# IMX7S_CPU_INTERFACES_2.net
KiCad netlist of a schematic drawn in Altium Designer
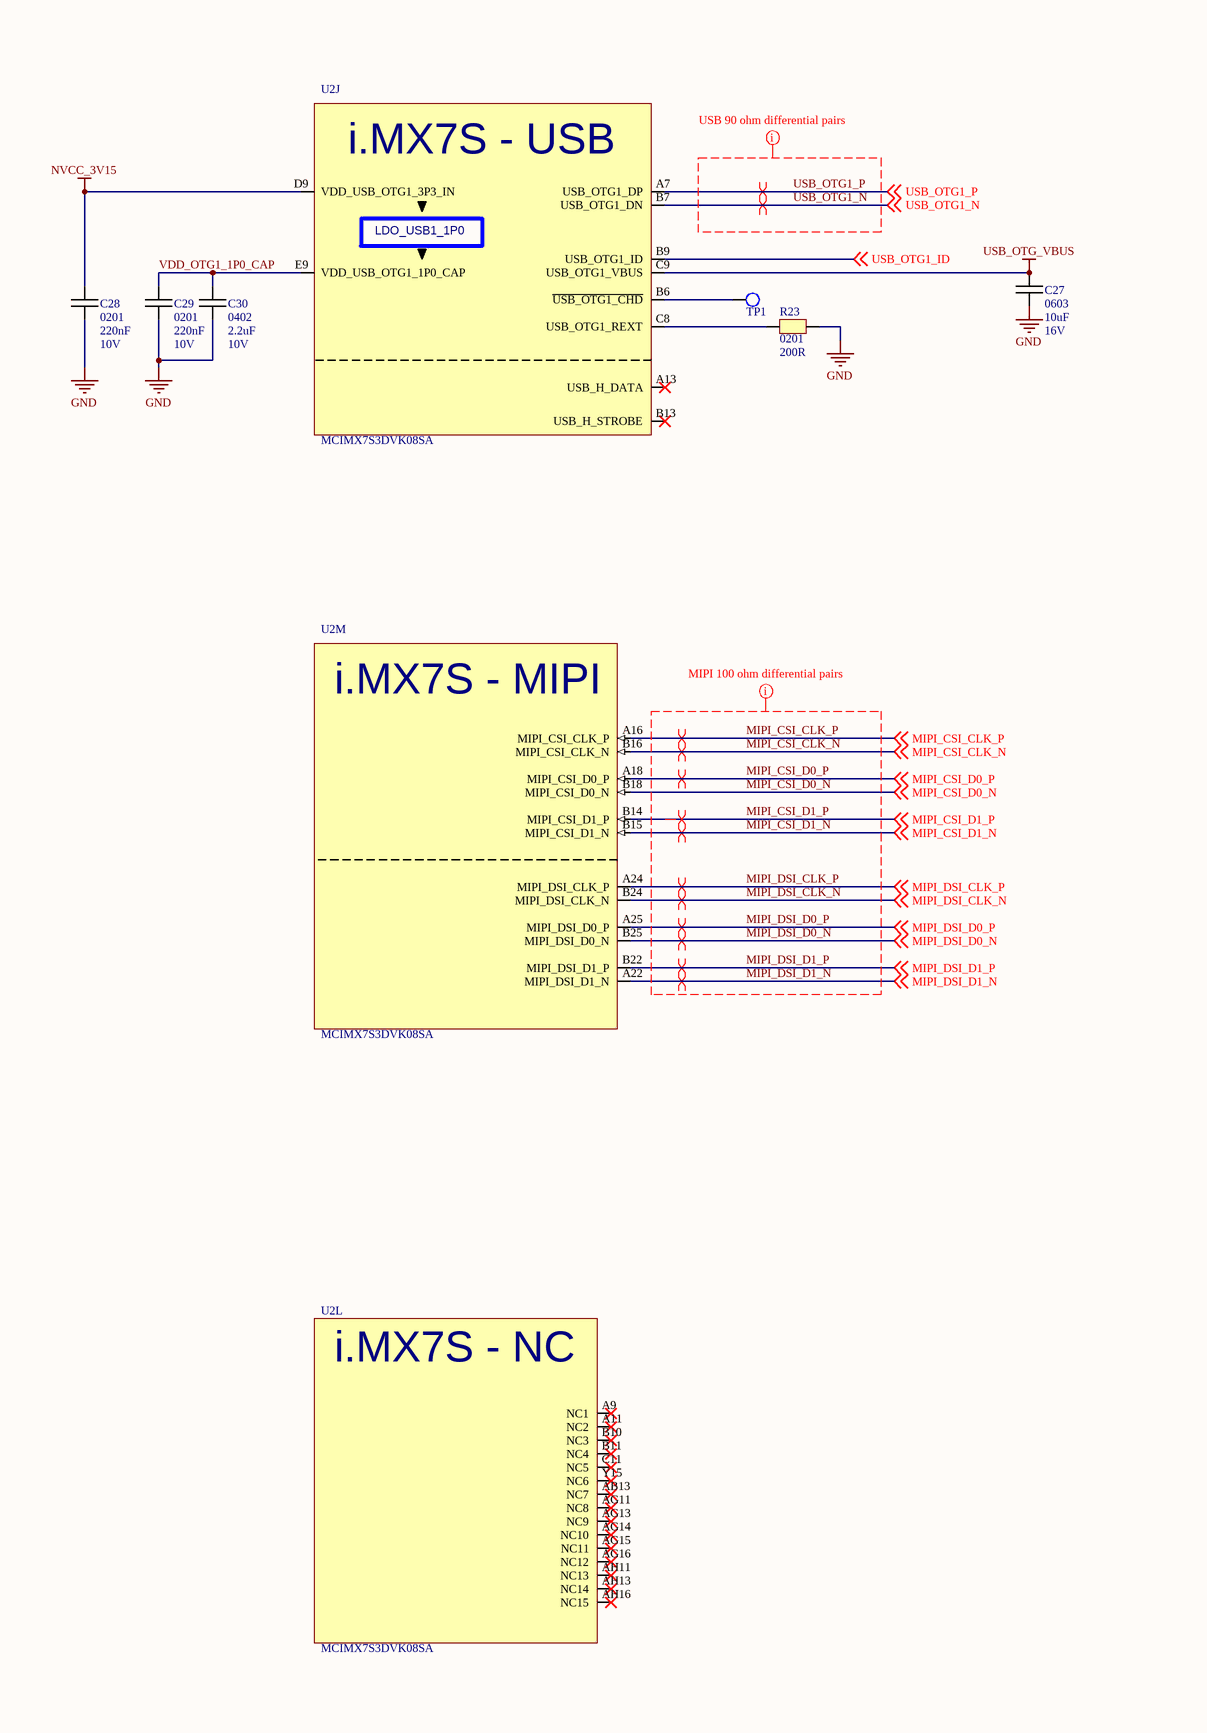
[diagram p0: IMX7S_CPU_INTERFACES_2.SchDoc, left]
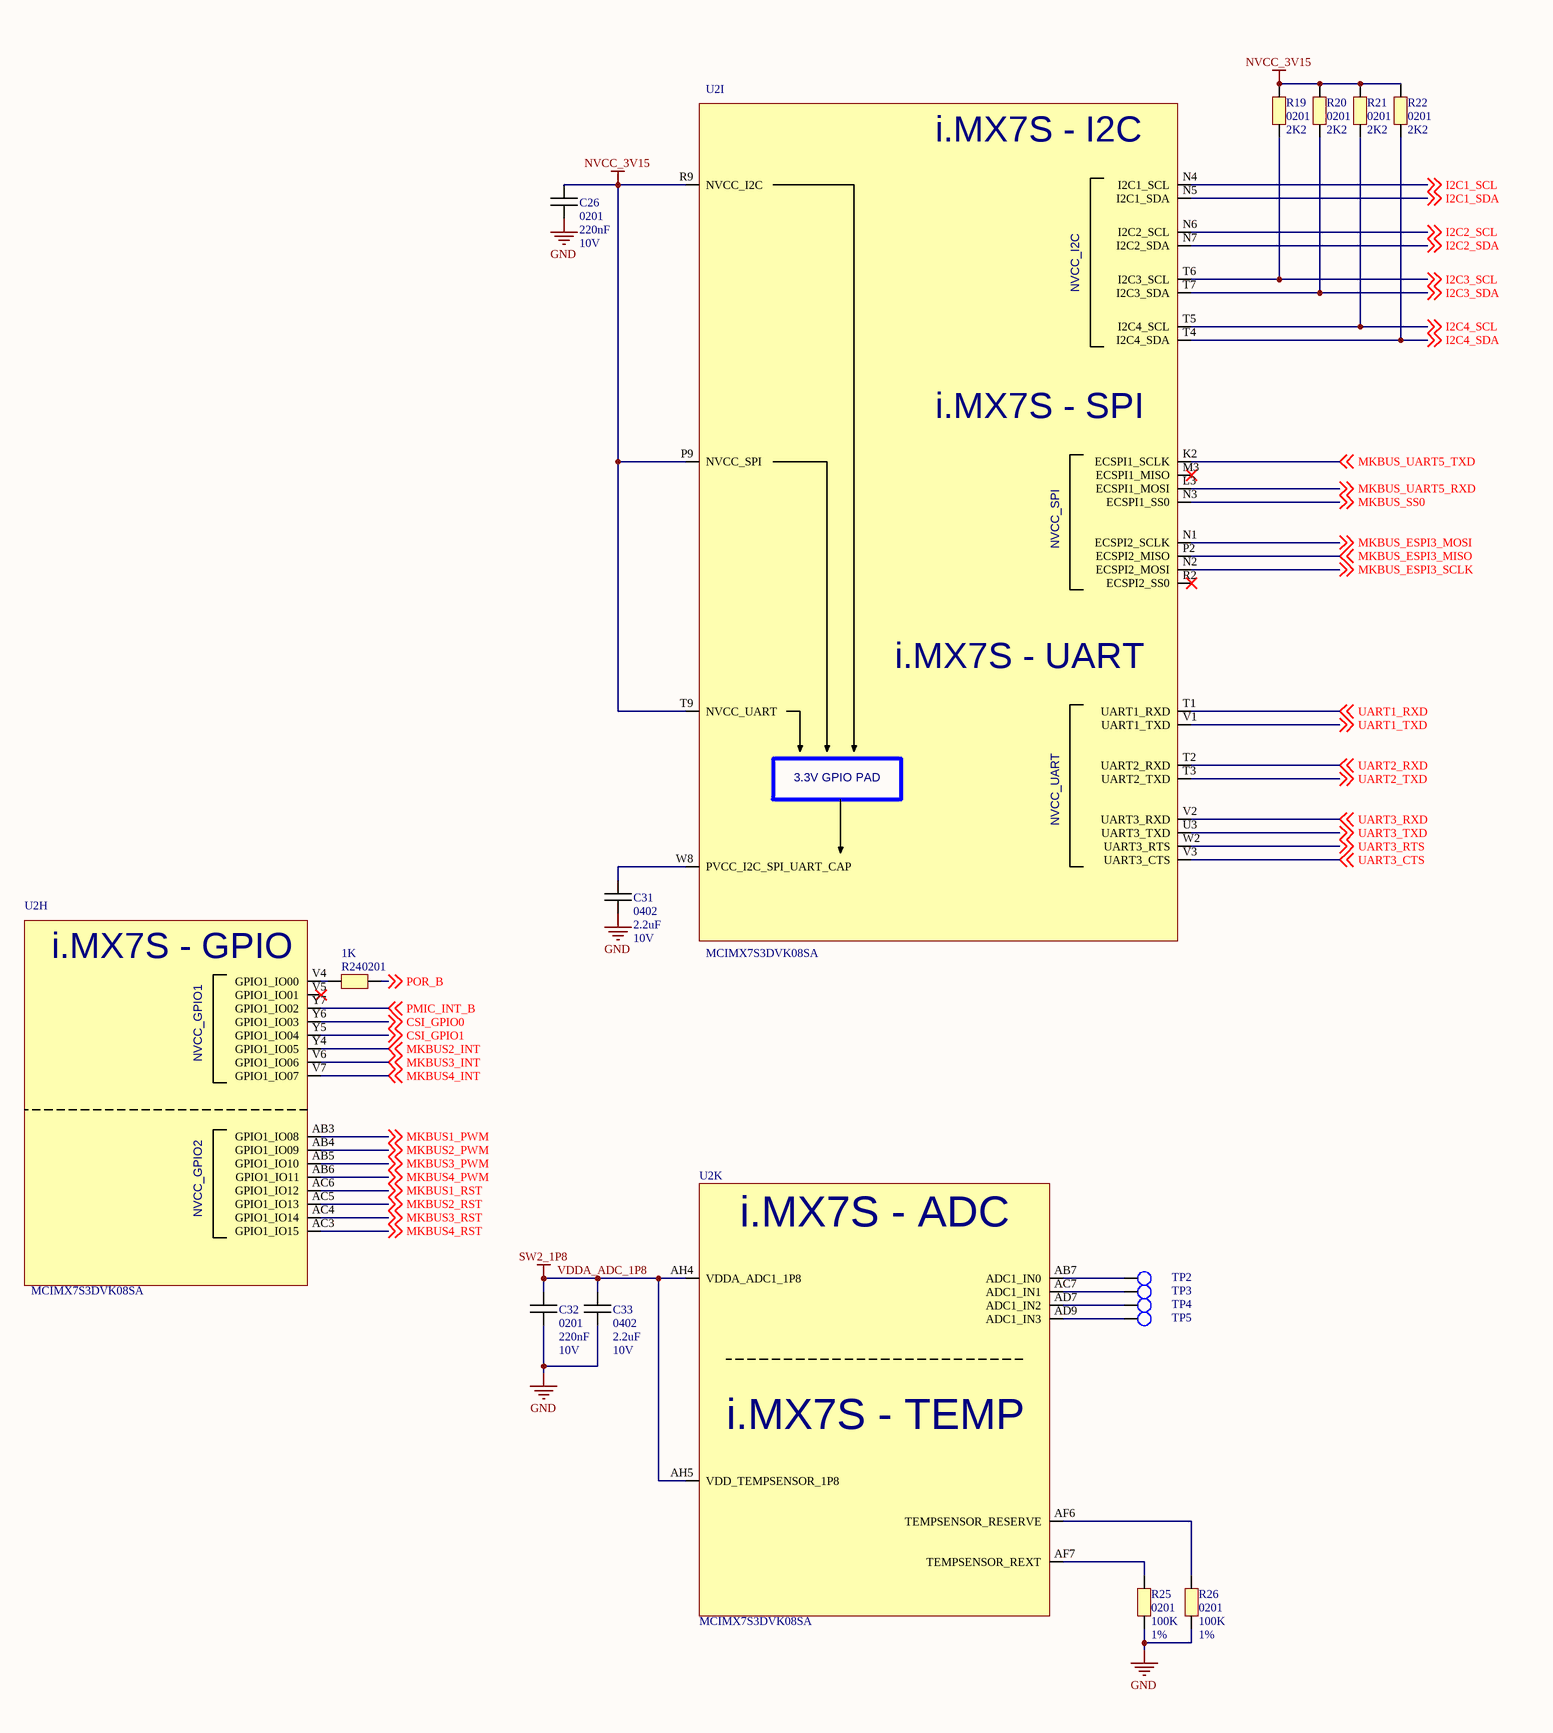
[diagram p1: IMX7S_CPU_INTERFACES_2.SchDoc, right]

(export (version "E")
  (design (tool "Eeschema 10.0.6"))
  (components
    (comp (ref "C26")
      (value "220nF")
      (footprint "C0201")
      (fields
        (field (name "PACKAGE") "0201")
        (field (name "VOLTAGE") "10V")
        (field (name "TOLERANCE") "10%")
        (field (name "Comment") "C0201")
      )
      (libsource (lib "Schlib_IMX7") (part "C0201"))
    )
    (comp (ref "C27")
      (value "10uF")
      (footprint "C0603")
      (description "Cap Ceramic 10uF 10V X5R 10% SMD 0603 85C Paper T/R")
      (fields
        (field (name "PACKAGE") "0603")
        (field (name "VOLTAGE") "16V")
        (field (name "TOLERANCE") "10%")
        (field (name "Comment") "C0603")
      )
      (libsource (lib "Schlib_IMX7") (part "C0603"))
    )
    (comp (ref "C28")
      (value "220nF")
      (footprint "C0201")
      (fields
        (field (name "PACKAGE") "0201")
        (field (name "VOLTAGE") "10V")
        (field (name "TOLERANCE") "10%")
        (field (name "Comment") "C0201")
      )
      (libsource (lib "Schlib_IMX7") (part "C0201"))
    )
    (comp (ref "C29")
      (value "220nF")
      (footprint "C0201")
      (fields
        (field (name "PACKAGE") "0201")
        (field (name "VOLTAGE") "10V")
        (field (name "TOLERANCE") "10%")
        (field (name "Comment") "C0201")
      )
      (libsource (lib "Schlib_IMX7") (part "C0201"))
    )
    (comp (ref "C30")
      (value "2.2uF")
      (footprint "C0402")
      (description "Cap Ceramic 2.2uF 10V X5R 10% SMD 0402 85C Paper T/R")
      (fields
        (field (name "PACKAGE") "0402")
        (field (name "VOLTAGE") "10V")
        (field (name "TOLERANCE") "10%")
        (field (name "Comment") "C0402")
      )
      (libsource (lib "Schlib_IMX7") (part "C0402"))
    )
    (comp (ref "C31")
      (value "2.2uF")
      (footprint "C0402")
      (fields
        (field (name "PACKAGE") "0402")
        (field (name "VOLTAGE") "10V")
        (field (name "TOLERANCE") "20%")
        (field (name "Comment") "C0402")
      )
      (libsource (lib "Schlib_IMX7") (part "C0402"))
    )
    (comp (ref "C32")
      (value "220nF")
      (footprint "C0201")
      (fields
        (field (name "PACKAGE") "0201")
        (field (name "VOLTAGE") "10V")
        (field (name "TOLERANCE") "10%")
        (field (name "Comment") "C0201")
      )
      (libsource (lib "Schlib_IMX7") (part "C0201"))
    )
    (comp (ref "C33")
      (value "2.2uF")
      (footprint "C0402")
      (fields
        (field (name "PACKAGE") "0402")
        (field (name "VOLTAGE") "10V")
        (field (name "TOLERANCE") "20%")
        (field (name "Comment") "C0402")
      )
      (libsource (lib "Schlib_IMX7") (part "C0402"))
    )
    (comp (ref "R19")
      (value "2K2")
      (footprint "R0201")
      (description "MULTICOMP - MCRE000148 - RES, 2K2, 1%, 0.05W, 0201, THICK FILM")
      (fields (field (name "PACKAGE") "0201") (field (name "VOLTAGE") "0V") (field (name "TOLERANCE") "1%"))
      (libsource (lib "Schlib_IMX7") (part "R0201"))
    )
    (comp (ref "R20")
      (value "2K2")
      (footprint "R0201")
      (description "MULTICOMP - MCRE000148 - RES, 2K2, 1%, 0.05W, 0201, THICK FILM")
      (fields (field (name "PACKAGE") "0201") (field (name "VOLTAGE") "0V") (field (name "TOLERANCE") "1%"))
      (libsource (lib "Schlib_IMX7") (part "R0201"))
    )
    (comp (ref "R21")
      (value "2K2")
      (footprint "R0201")
      (description "MULTICOMP - MCRE000148 - RES, 2K2, 1%, 0.05W, 0201, THICK FILM")
      (fields (field (name "PACKAGE") "0201") (field (name "VOLTAGE") "0V") (field (name "TOLERANCE") "1%"))
      (libsource (lib "Schlib_IMX7") (part "R0201"))
    )
    (comp (ref "R22")
      (value "2K2")
      (footprint "R0201")
      (description "MULTICOMP - MCRE000148 - RES, 2K2, 1%, 0.05W, 0201, THICK FILM")
      (fields (field (name "PACKAGE") "0201") (field (name "VOLTAGE") "0V") (field (name "TOLERANCE") "1%"))
      (libsource (lib "Schlib_IMX7") (part "R0201"))
    )
    (comp (ref "R23")
      (value "200R")
      (footprint "R0201")
      (fields
        (field (name "PACKAGE") "0201")
        (field (name "VOLTAGE") "0V")
        (field (name "TOLERANCE") "1%")
        (field (name "Comment") "R0201")
      )
      (libsource (lib "") (part "R0201_1"))
    )
    (comp (ref "R24")
      (value "1K")
      (footprint "R0201")
      (fields (field (name "PACKAGE") "0201") (field (name "VOLTAGE") "1%") (field (name "Comment") "R0201"))
      (libsource (lib "") (part "R0201_2"))
    )
    (comp (ref "R25")
      (value "100K")
      (footprint "R0201")
      (description "MULTICOMP - MCWR02X1003FAL - RES, 100K, 1%, 0.05W, THICK FILM")
      (fields
        (field (name "PACKAGE") "0201")
        (field (name "VOLTAGE") "1%")
        (field (name "TOLERANCE") "1%")
        (field (name "Comment") "R0201")
      )
      (libsource (lib "Schlib_IMX7") (part "R0201"))
    )
    (comp (ref "R26")
      (value "100K")
      (footprint "R0201")
      (description "MULTICOMP - MCWR02X1003FAL - RES, 100K, 1%, 0.05W, THICK FILM")
      (fields
        (field (name "PACKAGE") "0201")
        (field (name "VOLTAGE") "1%")
        (field (name "TOLERANCE") "1%")
        (field (name "Comment") "R0201")
      )
      (libsource (lib "Schlib_IMX7") (part "R0201"))
    )
    (comp (ref "TP1")
      (value "TestPoint")
      (footprint "TESTPOINT")
      (libsource (lib "Schlib_IMX7") (part "TestPoint"))
    )
    (comp (ref "TP2")
      (value "TestPoint")
      (footprint "TESTPOINT")
      (libsource (lib "Schlib_IMX7") (part "TestPoint"))
    )
    (comp (ref "TP3")
      (value "TestPoint")
      (footprint "TESTPOINT")
      (libsource (lib "Schlib_IMX7") (part "TestPoint"))
    )
    (comp (ref "TP4")
      (value "TestPoint")
      (footprint "TESTPOINT")
      (libsource (lib "Schlib_IMX7") (part "TestPoint"))
    )
    (comp (ref "TP5")
      (value "TestPoint")
      (footprint "TESTPOINT")
      (libsource (lib "Schlib_IMX7") (part "TestPoint"))
    )
    (comp (ref "U2")
      (value "MCIMX7S3DVK08SA")
      (footprint "BGA 488 PIN")
      (libsource (lib "Schlib_IMX7") (part "MCIMX7S3DVK08SD"))
    )
  )
  (nets
    (net (code "1") (name "/VDD_OTG1_1P0_CAP") (class "Default")
      (node (ref "C29") (pin "2") (pinfunction "2_2") (pintype "passive"))
      (node (ref "C30") (pin "2") (pinfunction "2_2") (pintype "passive"))
      (node (ref "U2") (pin "E9") (pinfunction "VDD_USB_OTG1_1P0_CAP_E9") (pintype "passive"))
    )
    (net (code "2") (name "CSI_GPIO0") (class "Default")
      (node (ref "U2") (pin "Y6") (pinfunction "GPIO1_IO03_Y6") (pintype "passive"))
    )
    (net (code "3") (name "CSI_GPIO1") (class "Default")
      (node (ref "U2") (pin "Y5") (pinfunction "GPIO1_IO04_Y5") (pintype "passive"))
    )
    (net (code "4") (name "GND") (class "Default")
      (node (ref "C26") (pin "1") (pinfunction "1_1") (pintype "passive"))
      (node (ref "C27") (pin "1") (pinfunction "1_1") (pintype "passive"))
      (node (ref "C28") (pin "1") (pinfunction "1_1") (pintype "passive"))
      (node (ref "C29") (pin "1") (pinfunction "1_1") (pintype "passive"))
      (node (ref "C30") (pin "1") (pinfunction "1_1") (pintype "passive"))
      (node (ref "C31") (pin "1") (pinfunction "1_1") (pintype "passive"))
      (node (ref "C32") (pin "1") (pinfunction "1_1") (pintype "passive"))
      (node (ref "C33") (pin "1") (pinfunction "1_1") (pintype "passive"))
      (node (ref "R23") (pin "2") (pinfunction "2_2") (pintype "passive"))
      (node (ref "R25") (pin "1") (pinfunction "1_1") (pintype "passive"))
      (node (ref "R26") (pin "1") (pinfunction "1_1") (pintype "passive"))
    )
    (net (code "5") (name "I2C1_SCL") (class "Default")
      (node (ref "U2") (pin "N4") (pinfunction "I2C1_SCL_N4") (pintype "passive"))
    )
    (net (code "6") (name "I2C1_SDA") (class "Default")
      (node (ref "U2") (pin "N5") (pinfunction "I2C1_SDA_N5") (pintype "passive"))
    )
    (net (code "7") (name "I2C2_SCL") (class "Default")
      (node (ref "U2") (pin "N6") (pinfunction "I2C2_SCL_N6") (pintype "passive"))
    )
    (net (code "8") (name "I2C2_SDA") (class "Default")
      (node (ref "U2") (pin "N7") (pinfunction "I2C2_SDA_N7") (pintype "passive"))
    )
    (net (code "9") (name "I2C3_SCL") (class "Default")
      (node (ref "R19") (pin "1") (pinfunction "1_1") (pintype "passive"))
      (node (ref "U2") (pin "T6") (pinfunction "I2C3_SCL_T6") (pintype "passive"))
    )
    (net (code "10") (name "I2C3_SDA") (class "Default")
      (node (ref "R20") (pin "1") (pinfunction "1_1") (pintype "passive"))
      (node (ref "U2") (pin "T7") (pinfunction "I2C3_SDA_T7") (pintype "passive"))
    )
    (net (code "11") (name "I2C4_SCL") (class "Default")
      (node (ref "R21") (pin "1") (pinfunction "1_1") (pintype "passive"))
      (node (ref "U2") (pin "T5") (pinfunction "I2C4_SCL_T5") (pintype "passive"))
    )
    (net (code "12") (name "I2C4_SDA") (class "Default")
      (node (ref "R22") (pin "1") (pinfunction "1_1") (pintype "passive"))
      (node (ref "U2") (pin "T4") (pinfunction "I2C4_SDA_T4") (pintype "passive"))
    )
    (net (code "13") (name "MIPI_CSI_CLK_N") (class "Default")
      (node (ref "U2") (pin "B16") (pinfunction "MIPI_CSI_CLK_N_B16") (pintype "input"))
    )
    (net (code "14") (name "MIPI_CSI_CLK_P") (class "Default")
      (node (ref "U2") (pin "A16") (pinfunction "MIPI_CSI_CLK_P_A16") (pintype "input"))
    )
    (net (code "15") (name "MIPI_CSI_D0_N") (class "Default")
      (node (ref "U2") (pin "B18") (pinfunction "MIPI_CSI_D0_N_B18") (pintype "input"))
    )
    (net (code "16") (name "MIPI_CSI_D0_P") (class "Default")
      (node (ref "U2") (pin "A18") (pinfunction "MIPI_CSI_D0_P_A18") (pintype "input"))
    )
    (net (code "17") (name "MIPI_CSI_D1_N") (class "Default")
      (node (ref "U2") (pin "B15") (pinfunction "MIPI_CSI_D1_N_B15") (pintype "input"))
    )
    (net (code "18") (name "MIPI_CSI_D1_P") (class "Default")
      (node (ref "U2") (pin "B14") (pinfunction "MIPI_CSI_D1_P_B14") (pintype "input"))
    )
    (net (code "19") (name "MIPI_DSI_CLK_N") (class "Default")
      (node (ref "U2") (pin "B24") (pinfunction "MIPI_DSI_CLK_N_B24") (pintype "passive"))
    )
    (net (code "20") (name "MIPI_DSI_CLK_P") (class "Default")
      (node (ref "U2") (pin "A24") (pinfunction "MIPI_DSI_CLK_P_A24") (pintype "passive"))
    )
    (net (code "21") (name "MIPI_DSI_D0_N") (class "Default")
      (node (ref "U2") (pin "B25") (pinfunction "MIPI_DSI_D0_N_B25") (pintype "passive"))
    )
    (net (code "22") (name "MIPI_DSI_D0_P") (class "Default")
      (node (ref "U2") (pin "A25") (pinfunction "MIPI_DSI_D0_P_A25") (pintype "passive"))
    )
    (net (code "23") (name "MIPI_DSI_D1_N") (class "Default")
      (node (ref "U2") (pin "A22") (pinfunction "MIPI_DSI_D1_N_A22") (pintype "passive"))
    )
    (net (code "24") (name "MIPI_DSI_D1_P") (class "Default")
      (node (ref "U2") (pin "B22") (pinfunction "MIPI_DSI_D1_P_B22") (pintype "passive"))
    )
    (net (code "25") (name "MKBUS1_PWM") (class "Default")
      (node (ref "U2") (pin "AB3") (pinfunction "GPIO1_IO08_AB3") (pintype "passive"))
    )
    (net (code "26") (name "MKBUS1_RST") (class "Default")
      (node (ref "U2") (pin "AC6") (pinfunction "GPIO1_IO12_AC6") (pintype "passive"))
    )
    (net (code "27") (name "MKBUS2_INT") (class "Default")
      (node (ref "U2") (pin "Y4") (pinfunction "GPIO1_IO05_Y4") (pintype "passive"))
    )
    (net (code "28") (name "MKBUS2_PWM") (class "Default")
      (node (ref "U2") (pin "AB4") (pinfunction "GPIO1_IO09_AB4") (pintype "passive"))
    )
    (net (code "29") (name "MKBUS2_RST") (class "Default")
      (node (ref "U2") (pin "AC5") (pinfunction "GPIO1_IO13_AC5") (pintype "passive"))
    )
    (net (code "30") (name "MKBUS3_INT") (class "Default")
      (node (ref "U2") (pin "V6") (pinfunction "GPIO1_IO06_V6") (pintype "passive"))
    )
    (net (code "31") (name "MKBUS3_PWM") (class "Default")
      (node (ref "U2") (pin "AB5") (pinfunction "GPIO1_IO10_AB5") (pintype "passive"))
    )
    (net (code "32") (name "MKBUS3_RST") (class "Default")
      (node (ref "U2") (pin "AC4") (pinfunction "GPIO1_IO14_AC4") (pintype "passive"))
    )
    (net (code "33") (name "MKBUS4_INT") (class "Default")
      (node (ref "U2") (pin "V7") (pinfunction "GPIO1_IO07_V7") (pintype "passive"))
    )
    (net (code "34") (name "MKBUS4_PWM") (class "Default")
      (node (ref "U2") (pin "AB6") (pinfunction "GPIO1_IO11_AB6") (pintype "passive"))
    )
    (net (code "35") (name "MKBUS4_RST") (class "Default")
      (node (ref "U2") (pin "AC3") (pinfunction "GPIO1_IO15_AC3") (pintype "passive"))
    )
    (net (code "36") (name "MKBUS_ESPI3_MISO") (class "Default")
      (node (ref "U2") (pin "P2") (pinfunction "ECSPI2_MISO_P2") (pintype "passive"))
    )
    (net (code "37") (name "MKBUS_ESPI3_MOSI") (class "Default")
      (node (ref "U2") (pin "N1") (pinfunction "ECSPI2_SCLK_N1") (pintype "passive"))
    )
    (net (code "38") (name "MKBUS_ESPI3_SCLK") (class "Default")
      (node (ref "U2") (pin "N2") (pinfunction "ECSPI2_MOSI_N2") (pintype "passive"))
    )
    (net (code "39") (name "MKBUS_SS0") (class "Default")
      (node (ref "U2") (pin "N3") (pinfunction "ECSPI1_SS0_N3") (pintype "passive"))
    )
    (net (code "40") (name "MKBUS_UART5_RXD") (class "Default")
      (node (ref "U2") (pin "L3") (pinfunction "ECSPI1_MOSI_L3") (pintype "passive"))
    )
    (net (code "41") (name "MKBUS_UART5_TXD") (class "Default")
      (node (ref "U2") (pin "K2") (pinfunction "ECSPI1_SCLK_K2") (pintype "passive"))
    )
    (net (code "42") (name "NVCC_3V15") (class "Default")
      (node (ref "C26") (pin "2") (pinfunction "2_2") (pintype "passive"))
      (node (ref "C28") (pin "2") (pinfunction "2_2") (pintype "passive"))
      (node (ref "R19") (pin "2") (pinfunction "2_2") (pintype "passive"))
      (node (ref "R20") (pin "2") (pinfunction "2_2") (pintype "passive"))
      (node (ref "R21") (pin "2") (pinfunction "2_2") (pintype "passive"))
      (node (ref "R22") (pin "2") (pinfunction "2_2") (pintype "passive"))
      (node (ref "U2") (pin "D9") (pinfunction "VDD_USB_OTG1_3P3_IN_D9") (pintype "passive"))
      (node (ref "U2") (pin "P9") (pinfunction "NVCC_SPI_P9") (pintype "passive"))
      (node (ref "U2") (pin "R9") (pinfunction "NVCC_I2C_R9") (pintype "passive"))
      (node (ref "U2") (pin "T9") (pinfunction "NVCC_UART_T9") (pintype "passive"))
    )
    (net (code "43") (name "Net-(U2H-GPIO1_IO00)") (class "Default")
      (node (ref "R24") (pin "2") (pinfunction "2_2") (pintype "passive"))
      (node (ref "U2") (pin "V4") (pinfunction "GPIO1_IO00_V4") (pintype "passive"))
    )
    (net (code "44") (name "Net-(U2I-PVCC_I2C_SPI_UART_CAP)") (class "Default")
      (node (ref "C31") (pin "2") (pinfunction "2_2") (pintype "passive"))
      (node (ref "U2") (pin "W8") (pinfunction "PVCC_I2C_SPI_UART_CAP_W8") (pintype "passive"))
    )
    (net (code "45") (name "Net-(U2J-USB_OTG1_REXT)") (class "Default")
      (node (ref "R23") (pin "1") (pinfunction "1_1") (pintype "passive"))
      (node (ref "U2") (pin "C8") (pinfunction "USB_OTG1_REXT_C8") (pintype "passive"))
    )
    (net (code "46") (name "Net-(U2J-~{USB_OTG1_CHD})") (class "Default")
      (node (ref "TP1") (pin "1") (pinfunction "1_1") (pintype "passive"))
      (node (ref "U2") (pin "B6") (pinfunction "~{USB_OTG1_CHD}_B6") (pintype "passive"))
    )
    (net (code "47") (name "Net-(U2K-ADC1_IN0)") (class "Default")
      (node (ref "TP2") (pin "1") (pinfunction "1_1") (pintype "passive"))
      (node (ref "U2") (pin "AB7") (pinfunction "ADC1_IN0_AB7") (pintype "passive"))
    )
    (net (code "48") (name "Net-(U2K-ADC1_IN1)") (class "Default")
      (node (ref "TP3") (pin "1") (pinfunction "1_1") (pintype "passive"))
      (node (ref "U2") (pin "AC7") (pinfunction "ADC1_IN1_AC7") (pintype "passive"))
    )
    (net (code "49") (name "Net-(U2K-ADC1_IN2)") (class "Default")
      (node (ref "TP4") (pin "1") (pinfunction "1_1") (pintype "passive"))
      (node (ref "U2") (pin "AD7") (pinfunction "ADC1_IN2_AD7") (pintype "passive"))
    )
    (net (code "50") (name "Net-(U2K-ADC1_IN3)") (class "Default")
      (node (ref "TP5") (pin "1") (pinfunction "1_1") (pintype "passive"))
      (node (ref "U2") (pin "AD9") (pinfunction "ADC1_IN3_AD9") (pintype "passive"))
    )
    (net (code "51") (name "Net-(U2K-TEMPSENSOR_RESERVE)") (class "Default")
      (node (ref "R26") (pin "2") (pinfunction "2_2") (pintype "passive"))
      (node (ref "U2") (pin "AF6") (pinfunction "TEMPSENSOR_RESERVE_AF6") (pintype "passive"))
    )
    (net (code "52") (name "Net-(U2K-TEMPSENSOR_REXT)") (class "Default")
      (node (ref "R25") (pin "2") (pinfunction "2_2") (pintype "passive"))
      (node (ref "U2") (pin "AF7") (pinfunction "TEMPSENSOR_REXT_AF7") (pintype "passive"))
    )
    (net (code "53") (name "PMIC_INT_B") (class "Default")
      (node (ref "U2") (pin "Y7") (pinfunction "GPIO1_IO02_Y7") (pintype "passive"))
    )
    (net (code "54") (name "POR_B") (class "Default")
      (node (ref "R24") (pin "1") (pinfunction "1_1") (pintype "passive"))
    )
    (net (code "55") (name "SW2_1P8") (class "Default")
      (node (ref "C32") (pin "2") (pinfunction "2_2") (pintype "passive"))
      (node (ref "C33") (pin "2") (pinfunction "2_2") (pintype "passive"))
      (node (ref "U2") (pin "AH4") (pinfunction "VDDA_ADC1_1P8_AH4") (pintype "passive"))
      (node (ref "U2") (pin "AH5") (pinfunction "VDD_TEMPSENSOR_1P8_AH5") (pintype "passive"))
    )
    (net (code "56") (name "UART1_RXD") (class "Default")
      (node (ref "U2") (pin "T1") (pinfunction "UART1_RXD_T1") (pintype "passive"))
    )
    (net (code "57") (name "UART1_TXD") (class "Default")
      (node (ref "U2") (pin "V1") (pinfunction "UART1_TXD_V1") (pintype "passive"))
    )
    (net (code "58") (name "UART2_RXD") (class "Default")
      (node (ref "U2") (pin "T2") (pinfunction "UART2_RXD_T2") (pintype "passive"))
    )
    (net (code "59") (name "UART2_TXD") (class "Default")
      (node (ref "U2") (pin "T3") (pinfunction "UART2_TXD_T3") (pintype "passive"))
    )
    (net (code "60") (name "UART3_CTS") (class "Default")
      (node (ref "U2") (pin "V3") (pinfunction "UART3_CTS_V3") (pintype "passive"))
    )
    (net (code "61") (name "UART3_RTS") (class "Default")
      (node (ref "U2") (pin "W2") (pinfunction "UART3_RTS_W2") (pintype "passive"))
    )
    (net (code "62") (name "UART3_RXD") (class "Default")
      (node (ref "U2") (pin "V2") (pinfunction "UART3_RXD_V2") (pintype "passive"))
    )
    (net (code "63") (name "UART3_TXD") (class "Default")
      (node (ref "U2") (pin "U3") (pinfunction "UART3_TXD_U3") (pintype "passive"))
    )
    (net (code "64") (name "USB_OTG1_ID") (class "Default")
      (node (ref "U2") (pin "B9") (pinfunction "USB_OTG1_ID_B9") (pintype "passive"))
    )
    (net (code "65") (name "USB_OTG1_N") (class "Default")
      (node (ref "U2") (pin "B7") (pinfunction "USB_OTG1_DN_B7") (pintype "passive"))
    )
    (net (code "66") (name "USB_OTG1_P") (class "Default")
      (node (ref "U2") (pin "A7") (pinfunction "USB_OTG1_DP_A7") (pintype "passive"))
    )
    (net (code "67") (name "USB_OTG_VBUS") (class "Default")
      (node (ref "C27") (pin "2") (pinfunction "2_2") (pintype "passive"))
      (node (ref "U2") (pin "C9") (pinfunction "USB_OTG1_VBUS_C9") (pintype "passive"))
    )
    (net (code "68") (name "unconnected-(U2H-GPIO1_IO01-PadV5)") (class "Default")
      (node (ref "U2") (pin "V5") (pinfunction "GPIO1_IO01_V5") (pintype "passive+no_connect"))
    )
    (net (code "69") (name "unconnected-(U2I-ECSPI1_MISO-PadM3)") (class "Default")
      (node (ref "U2") (pin "M3") (pinfunction "ECSPI1_MISO_M3") (pintype "passive+no_connect"))
    )
    (net (code "70") (name "unconnected-(U2I-ECSPI2_SS0-PadR2)") (class "Default")
      (node (ref "U2") (pin "R2") (pinfunction "ECSPI2_SS0_R2") (pintype "passive+no_connect"))
    )
    (net (code "71") (name "unconnected-(U2J-USB_H_DATA-PadA13)") (class "Default")
      (node (ref "U2") (pin "A13") (pinfunction "USB_H_DATA_A13") (pintype "passive+no_connect"))
    )
    (net (code "72") (name "unconnected-(U2J-USB_H_STROBE-PadB13)") (class "Default")
      (node (ref "U2") (pin "B13") (pinfunction "USB_H_STROBE_B13") (pintype "passive+no_connect"))
    )
    (net (code "73") (name "unconnected-(U2L-NC1-PadA9)") (class "Default")
      (node (ref "U2") (pin "A9") (pinfunction "NC1_A9") (pintype "passive+no_connect"))
    )
    (net (code "74") (name "unconnected-(U2L-NC2-PadA11)") (class "Default")
      (node (ref "U2") (pin "A11") (pinfunction "NC2_A11") (pintype "passive+no_connect"))
    )
    (net (code "75") (name "unconnected-(U2L-NC3-PadB10)") (class "Default")
      (node (ref "U2") (pin "B10") (pinfunction "NC3_B10") (pintype "passive+no_connect"))
    )
    (net (code "76") (name "unconnected-(U2L-NC4-PadB11)") (class "Default")
      (node (ref "U2") (pin "B11") (pinfunction "NC4_B11") (pintype "passive+no_connect"))
    )
    (net (code "77") (name "unconnected-(U2L-NC5-PadC11)") (class "Default")
      (node (ref "U2") (pin "C11") (pinfunction "NC5_C11") (pintype "passive+no_connect"))
    )
    (net (code "78") (name "unconnected-(U2L-NC6-PadY15)") (class "Default")
      (node (ref "U2") (pin "Y15") (pinfunction "NC6_Y15") (pintype "passive+no_connect"))
    )
    (net (code "79") (name "unconnected-(U2L-NC7-PadAB13)") (class "Default")
      (node (ref "U2") (pin "AB13") (pinfunction "NC7_AB13") (pintype "passive+no_connect"))
    )
    (net (code "80") (name "unconnected-(U2L-NC8-PadAG11)") (class "Default")
      (node (ref "U2") (pin "AG11") (pinfunction "NC8_AG11") (pintype "passive+no_connect"))
    )
    (net (code "81") (name "unconnected-(U2L-NC9-PadAG13)") (class "Default")
      (node (ref "U2") (pin "AG13") (pinfunction "NC9_AG13") (pintype "passive+no_connect"))
    )
    (net (code "82") (name "unconnected-(U2L-NC10-PadAG14)") (class "Default")
      (node (ref "U2") (pin "AG14") (pinfunction "NC10_AG14") (pintype "passive+no_connect"))
    )
    (net (code "83") (name "unconnected-(U2L-NC11-PadAG15)") (class "Default")
      (node (ref "U2") (pin "AG15") (pinfunction "NC11_AG15") (pintype "passive+no_connect"))
    )
    (net (code "84") (name "unconnected-(U2L-NC12-PadAG16)") (class "Default")
      (node (ref "U2") (pin "AG16") (pinfunction "NC12_AG16") (pintype "passive+no_connect"))
    )
    (net (code "85") (name "unconnected-(U2L-NC13-PadAH11)") (class "Default")
      (node (ref "U2") (pin "AH11") (pinfunction "NC13_AH11") (pintype "passive+no_connect"))
    )
    (net (code "86") (name "unconnected-(U2L-NC14-PadAH13)") (class "Default")
      (node (ref "U2") (pin "AH13") (pinfunction "NC14_AH13") (pintype "passive+no_connect"))
    )
    (net (code "87") (name "unconnected-(U2L-NC15-PadAH16)") (class "Default")
      (node (ref "U2") (pin "AH16") (pinfunction "NC15_AH16") (pintype "passive+no_connect"))
    )
  )
)
